# schemat-eagle.net
KiCad netlist of a schematic drawn in EAGLE
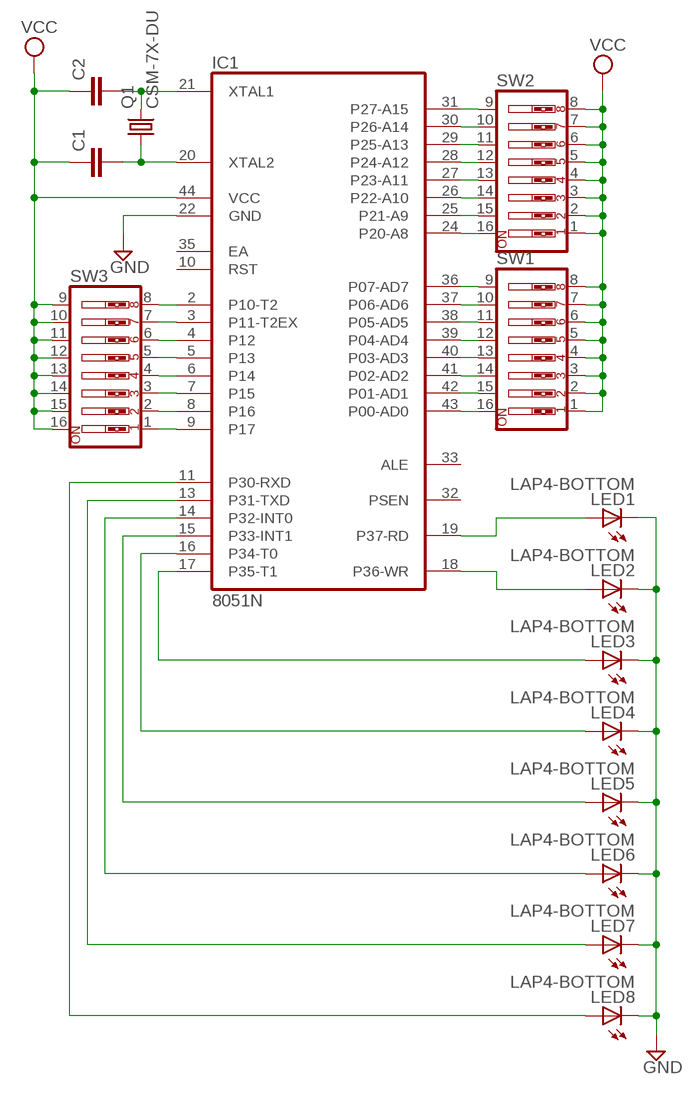
[diagram p0: schematic, sheet 1]

(export (version "E")
  (design (tool "Eeschema 10.0.6"))
  (components
    (comp (ref "C1")
      (value "C22/6")
      (footprint "eagle-import:C22.5B6")
      (libsource (lib "eagle-import") (part "C22/6"))
    )
    (comp (ref "C2")
      (value "C22/6")
      (footprint "eagle-import:C22.5B6")
      (libsource (lib "eagle-import") (part "C22/6"))
    )
    (comp (ref "IC1")
      (value "8051N")
      (footprint "eagle-import:PLCC44")
      (libsource (lib "eagle-import") (part "8051N"))
    )
    (comp (ref "LED1")
      (value "LAP4-BOTTOM")
      (footprint "eagle-import:P47F-BOTTOM")
      (libsource (lib "eagle-import") (part "P4-BOTTOMLA"))
    )
    (comp (ref "LED2")
      (value "LAP4-BOTTOM")
      (footprint "eagle-import:P47F-BOTTOM")
      (libsource (lib "eagle-import") (part "P4-BOTTOMLA"))
    )
    (comp (ref "LED3")
      (value "LAP4-BOTTOM")
      (footprint "eagle-import:P47F-BOTTOM")
      (libsource (lib "eagle-import") (part "P4-BOTTOMLA"))
    )
    (comp (ref "LED4")
      (value "LAP4-BOTTOM")
      (footprint "eagle-import:P47F-BOTTOM")
      (libsource (lib "eagle-import") (part "P4-BOTTOMLA"))
    )
    (comp (ref "LED5")
      (value "LAP4-BOTTOM")
      (footprint "eagle-import:P47F-BOTTOM")
      (libsource (lib "eagle-import") (part "P4-BOTTOMLA"))
    )
    (comp (ref "LED6")
      (value "LAP4-BOTTOM")
      (footprint "eagle-import:P47F-BOTTOM")
      (libsource (lib "eagle-import") (part "P4-BOTTOMLA"))
    )
    (comp (ref "LED7")
      (value "LAP4-BOTTOM")
      (footprint "eagle-import:P47F-BOTTOM")
      (libsource (lib "eagle-import") (part "P4-BOTTOMLA"))
    )
    (comp (ref "LED8")
      (value "LAP4-BOTTOM")
      (footprint "eagle-import:P47F-BOTTOM")
      (libsource (lib "eagle-import") (part "P4-BOTTOMLA"))
    )
    (comp (ref "Q1")
      (value "CSM-7X-DU")
      (footprint "eagle-import:CSM-7X-DU")
      (libsource (lib "eagle-import") (part "CSM-7X-DU"))
    )
    (comp (ref "SW1")
      (value "SW_DIP-8")
      (footprint "eagle-import:EDG-08")
      (libsource (lib "eagle-import") (part "SW_DIP-8"))
    )
    (comp (ref "SW2")
      (value "SW_DIP-8")
      (footprint "eagle-import:EDG-08")
      (libsource (lib "eagle-import") (part "SW_DIP-8"))
    )
    (comp (ref "SW3")
      (value "SW_DIP-8")
      (footprint "eagle-import:EDG-08")
      (libsource (lib "eagle-import") (part "SW_DIP-8"))
    )
  )
  (nets
    (net (code "1") (name "GND") (class "Default")
      (node (ref "IC1") (pin "22") (pinfunction "GND_22") (pintype "power_in"))
      (node (ref "LED1") (pin "C") (pinfunction "C_C") (pintype "passive"))
      (node (ref "LED2") (pin "C") (pinfunction "C_C") (pintype "passive"))
      (node (ref "LED3") (pin "C") (pinfunction "C_C") (pintype "passive"))
      (node (ref "LED4") (pin "C") (pinfunction "C_C") (pintype "passive"))
      (node (ref "LED5") (pin "C") (pinfunction "C_C") (pintype "passive"))
      (node (ref "LED6") (pin "C") (pinfunction "C_C") (pintype "passive"))
      (node (ref "LED7") (pin "C") (pinfunction "C_C") (pintype "passive"))
      (node (ref "LED8") (pin "C") (pinfunction "C_C") (pintype "passive"))
    )
    (net (code "2") (name "Net-(IC1-P00-AD0)") (class "Default")
      (node (ref "IC1") (pin "43") (pinfunction "P00-AD0_43") (pintype "bidirectional"))
      (node (ref "SW1") (pin "16") (pinfunction "16_16") (pintype "passive"))
    )
    (net (code "3") (name "Net-(IC1-P01-AD1)") (class "Default")
      (node (ref "IC1") (pin "42") (pinfunction "P01-AD1_42") (pintype "bidirectional"))
      (node (ref "SW1") (pin "15") (pinfunction "15_15") (pintype "passive"))
    )
    (net (code "4") (name "Net-(IC1-P02-AD2)") (class "Default")
      (node (ref "IC1") (pin "41") (pinfunction "P02-AD2_41") (pintype "bidirectional"))
      (node (ref "SW1") (pin "14") (pinfunction "14_14") (pintype "passive"))
    )
    (net (code "5") (name "Net-(IC1-P03-AD3)") (class "Default")
      (node (ref "IC1") (pin "40") (pinfunction "P03-AD3_40") (pintype "bidirectional"))
      (node (ref "SW1") (pin "13") (pinfunction "13_13") (pintype "passive"))
    )
    (net (code "6") (name "Net-(IC1-P04-AD4)") (class "Default")
      (node (ref "IC1") (pin "39") (pinfunction "P04-AD4_39") (pintype "bidirectional"))
      (node (ref "SW1") (pin "12") (pinfunction "12_12") (pintype "passive"))
    )
    (net (code "7") (name "Net-(IC1-P05-AD5)") (class "Default")
      (node (ref "IC1") (pin "38") (pinfunction "P05-AD5_38") (pintype "bidirectional"))
      (node (ref "SW1") (pin "11") (pinfunction "11_11") (pintype "passive"))
    )
    (net (code "8") (name "Net-(IC1-P06-AD6)") (class "Default")
      (node (ref "IC1") (pin "37") (pinfunction "P06-AD6_37") (pintype "bidirectional"))
      (node (ref "SW1") (pin "10") (pinfunction "10_10") (pintype "passive"))
    )
    (net (code "9") (name "Net-(IC1-P07-AD7)") (class "Default")
      (node (ref "IC1") (pin "36") (pinfunction "P07-AD7_36") (pintype "bidirectional"))
      (node (ref "SW1") (pin "9") (pinfunction "9_9") (pintype "passive"))
    )
    (net (code "10") (name "Net-(IC1-P10-T2)") (class "Default")
      (node (ref "IC1") (pin "2") (pinfunction "P10-T2_2") (pintype "bidirectional"))
      (node (ref "SW3") (pin "8") (pinfunction "8_8") (pintype "passive"))
    )
    (net (code "11") (name "Net-(IC1-P11-T2EX)") (class "Default")
      (node (ref "IC1") (pin "3") (pinfunction "P11-T2EX_3") (pintype "bidirectional"))
      (node (ref "SW3") (pin "7") (pinfunction "7_7") (pintype "passive"))
    )
    (net (code "12") (name "Net-(IC1-P12)") (class "Default")
      (node (ref "IC1") (pin "4") (pinfunction "P12_4") (pintype "bidirectional"))
      (node (ref "SW3") (pin "6") (pinfunction "6_6") (pintype "passive"))
    )
    (net (code "13") (name "Net-(IC1-P13)") (class "Default")
      (node (ref "IC1") (pin "5") (pinfunction "P13_5") (pintype "bidirectional"))
      (node (ref "SW3") (pin "5") (pinfunction "5_5") (pintype "passive"))
    )
    (net (code "14") (name "Net-(IC1-P14)") (class "Default")
      (node (ref "IC1") (pin "6") (pinfunction "P14_6") (pintype "bidirectional"))
      (node (ref "SW3") (pin "4") (pinfunction "4_4") (pintype "passive"))
    )
    (net (code "15") (name "Net-(IC1-P15)") (class "Default")
      (node (ref "IC1") (pin "7") (pinfunction "P15_7") (pintype "bidirectional"))
      (node (ref "SW3") (pin "3") (pinfunction "3_3") (pintype "passive"))
    )
    (net (code "16") (name "Net-(IC1-P16)") (class "Default")
      (node (ref "IC1") (pin "8") (pinfunction "P16_8") (pintype "bidirectional"))
      (node (ref "SW3") (pin "2") (pinfunction "2_2") (pintype "passive"))
    )
    (net (code "17") (name "Net-(IC1-P17)") (class "Default")
      (node (ref "IC1") (pin "9") (pinfunction "P17_9") (pintype "bidirectional"))
      (node (ref "SW3") (pin "1") (pinfunction "1_1") (pintype "passive"))
    )
    (net (code "18") (name "Net-(IC1-P20-A8)") (class "Default")
      (node (ref "IC1") (pin "24") (pinfunction "P20-A8_24") (pintype "bidirectional"))
      (node (ref "SW2") (pin "16") (pinfunction "16_16") (pintype "passive"))
    )
    (net (code "19") (name "Net-(IC1-P21-A9)") (class "Default")
      (node (ref "IC1") (pin "25") (pinfunction "P21-A9_25") (pintype "bidirectional"))
      (node (ref "SW2") (pin "15") (pinfunction "15_15") (pintype "passive"))
    )
    (net (code "20") (name "Net-(IC1-P22-A10)") (class "Default")
      (node (ref "IC1") (pin "26") (pinfunction "P22-A10_26") (pintype "bidirectional"))
      (node (ref "SW2") (pin "14") (pinfunction "14_14") (pintype "passive"))
    )
    (net (code "21") (name "Net-(IC1-P23-A11)") (class "Default")
      (node (ref "IC1") (pin "27") (pinfunction "P23-A11_27") (pintype "bidirectional"))
      (node (ref "SW2") (pin "13") (pinfunction "13_13") (pintype "passive"))
    )
    (net (code "22") (name "Net-(IC1-P24-A12)") (class "Default")
      (node (ref "IC1") (pin "28") (pinfunction "P24-A12_28") (pintype "bidirectional"))
      (node (ref "SW2") (pin "12") (pinfunction "12_12") (pintype "passive"))
    )
    (net (code "23") (name "Net-(IC1-P25-A13)") (class "Default")
      (node (ref "IC1") (pin "29") (pinfunction "P25-A13_29") (pintype "bidirectional"))
      (node (ref "SW2") (pin "11") (pinfunction "11_11") (pintype "passive"))
    )
    (net (code "24") (name "Net-(IC1-P26-A14)") (class "Default")
      (node (ref "IC1") (pin "30") (pinfunction "P26-A14_30") (pintype "bidirectional"))
      (node (ref "SW2") (pin "10") (pinfunction "10_10") (pintype "passive"))
    )
    (net (code "25") (name "Net-(IC1-P27-A15)") (class "Default")
      (node (ref "IC1") (pin "31") (pinfunction "P27-A15_31") (pintype "bidirectional"))
      (node (ref "SW2") (pin "9") (pinfunction "9_9") (pintype "passive"))
    )
    (net (code "26") (name "Net-(IC1-P30-RXD)") (class "Default")
      (node (ref "IC1") (pin "11") (pinfunction "P30-RXD_11") (pintype "bidirectional"))
      (node (ref "LED8") (pin "A") (pinfunction "A_A") (pintype "passive"))
    )
    (net (code "27") (name "Net-(IC1-P31-TXD)") (class "Default")
      (node (ref "IC1") (pin "13") (pinfunction "P31-TXD_13") (pintype "bidirectional"))
      (node (ref "LED7") (pin "A") (pinfunction "A_A") (pintype "passive"))
    )
    (net (code "28") (name "Net-(IC1-P32-INT0)") (class "Default")
      (node (ref "IC1") (pin "14") (pinfunction "P32-INT0_14") (pintype "bidirectional"))
      (node (ref "LED6") (pin "A") (pinfunction "A_A") (pintype "passive"))
    )
    (net (code "29") (name "Net-(IC1-P33-INT1)") (class "Default")
      (node (ref "IC1") (pin "15") (pinfunction "P33-INT1_15") (pintype "bidirectional"))
      (node (ref "LED5") (pin "A") (pinfunction "A_A") (pintype "passive"))
    )
    (net (code "30") (name "Net-(IC1-P34-T0)") (class "Default")
      (node (ref "IC1") (pin "16") (pinfunction "P34-T0_16") (pintype "bidirectional"))
      (node (ref "LED4") (pin "A") (pinfunction "A_A") (pintype "passive"))
    )
    (net (code "31") (name "Net-(IC1-P35-T1)") (class "Default")
      (node (ref "IC1") (pin "17") (pinfunction "P35-T1_17") (pintype "bidirectional"))
      (node (ref "LED3") (pin "A") (pinfunction "A_A") (pintype "passive"))
    )
    (net (code "32") (name "Net-(IC1-P36-WR)") (class "Default")
      (node (ref "IC1") (pin "18") (pinfunction "P36-WR_18") (pintype "bidirectional"))
      (node (ref "LED2") (pin "A") (pinfunction "A_A") (pintype "passive"))
    )
    (net (code "33") (name "Net-(IC1-P37-RD)") (class "Default")
      (node (ref "IC1") (pin "19") (pinfunction "P37-RD_19") (pintype "bidirectional"))
      (node (ref "LED1") (pin "A") (pinfunction "A_A") (pintype "passive"))
    )
    (net (code "34") (name "Net-(IC1-XTAL1)") (class "Default")
      (node (ref "C2") (pin "2") (pinfunction "2_2") (pintype "passive"))
      (node (ref "IC1") (pin "21") (pinfunction "XTAL1_21") (pintype "input"))
      (node (ref "Q1") (pin "2") (pinfunction "2_2") (pintype "passive"))
    )
    (net (code "35") (name "Net-(IC1-XTAL2)") (class "Default")
      (node (ref "C1") (pin "2") (pinfunction "2_2") (pintype "passive"))
      (node (ref "IC1") (pin "20") (pinfunction "XTAL2_20") (pintype "input"))
      (node (ref "Q1") (pin "1") (pinfunction "1_1") (pintype "passive"))
    )
    (net (code "36") (name "VCC") (class "Default")
      (node (ref "C1") (pin "1") (pinfunction "1_1") (pintype "passive"))
      (node (ref "C2") (pin "1") (pinfunction "1_1") (pintype "passive"))
      (node (ref "IC1") (pin "44") (pinfunction "VCC_44") (pintype "power_in"))
      (node (ref "SW1") (pin "1") (pinfunction "1_1") (pintype "passive"))
      (node (ref "SW1") (pin "2") (pinfunction "2_2") (pintype "passive"))
      (node (ref "SW1") (pin "3") (pinfunction "3_3") (pintype "passive"))
      (node (ref "SW1") (pin "4") (pinfunction "4_4") (pintype "passive"))
      (node (ref "SW1") (pin "5") (pinfunction "5_5") (pintype "passive"))
      (node (ref "SW1") (pin "6") (pinfunction "6_6") (pintype "passive"))
      (node (ref "SW1") (pin "7") (pinfunction "7_7") (pintype "passive"))
      (node (ref "SW1") (pin "8") (pinfunction "8_8") (pintype "passive"))
      (node (ref "SW2") (pin "1") (pinfunction "1_1") (pintype "passive"))
      (node (ref "SW2") (pin "2") (pinfunction "2_2") (pintype "passive"))
      (node (ref "SW2") (pin "3") (pinfunction "3_3") (pintype "passive"))
      (node (ref "SW2") (pin "4") (pinfunction "4_4") (pintype "passive"))
      (node (ref "SW2") (pin "5") (pinfunction "5_5") (pintype "passive"))
      (node (ref "SW2") (pin "6") (pinfunction "6_6") (pintype "passive"))
      (node (ref "SW2") (pin "7") (pinfunction "7_7") (pintype "passive"))
      (node (ref "SW2") (pin "8") (pinfunction "8_8") (pintype "passive"))
      (node (ref "SW3") (pin "10") (pinfunction "10_10") (pintype "passive"))
      (node (ref "SW3") (pin "11") (pinfunction "11_11") (pintype "passive"))
      (node (ref "SW3") (pin "12") (pinfunction "12_12") (pintype "passive"))
      (node (ref "SW3") (pin "13") (pinfunction "13_13") (pintype "passive"))
      (node (ref "SW3") (pin "14") (pinfunction "14_14") (pintype "passive"))
      (node (ref "SW3") (pin "15") (pinfunction "15_15") (pintype "passive"))
      (node (ref "SW3") (pin "16") (pinfunction "16_16") (pintype "passive"))
      (node (ref "SW3") (pin "9") (pinfunction "9_9") (pintype "passive"))
    )
    (net (code "37") (name "unconnected-(IC1-ALE-Pad33)") (class "Default")
      (node (ref "IC1") (pin "33") (pinfunction "ALE_33") (pintype "output"))
    )
    (net (code "38") (name "unconnected-(IC1-EA-Pad35)") (class "Default")
      (node (ref "IC1") (pin "35") (pinfunction "EA_35") (pintype "input"))
    )
    (net (code "39") (name "unconnected-(IC1-PSEN-Pad32)") (class "Default")
      (node (ref "IC1") (pin "32") (pinfunction "PSEN_32") (pintype "output"))
    )
    (net (code "40") (name "unconnected-(IC1-RST-Pad10)") (class "Default")
      (node (ref "IC1") (pin "10") (pinfunction "RST_10") (pintype "input"))
    )
  )
)
